# seq_s-h_1-13-21-fix.net
KiCad netlist of a schematic drawn in EAGLE
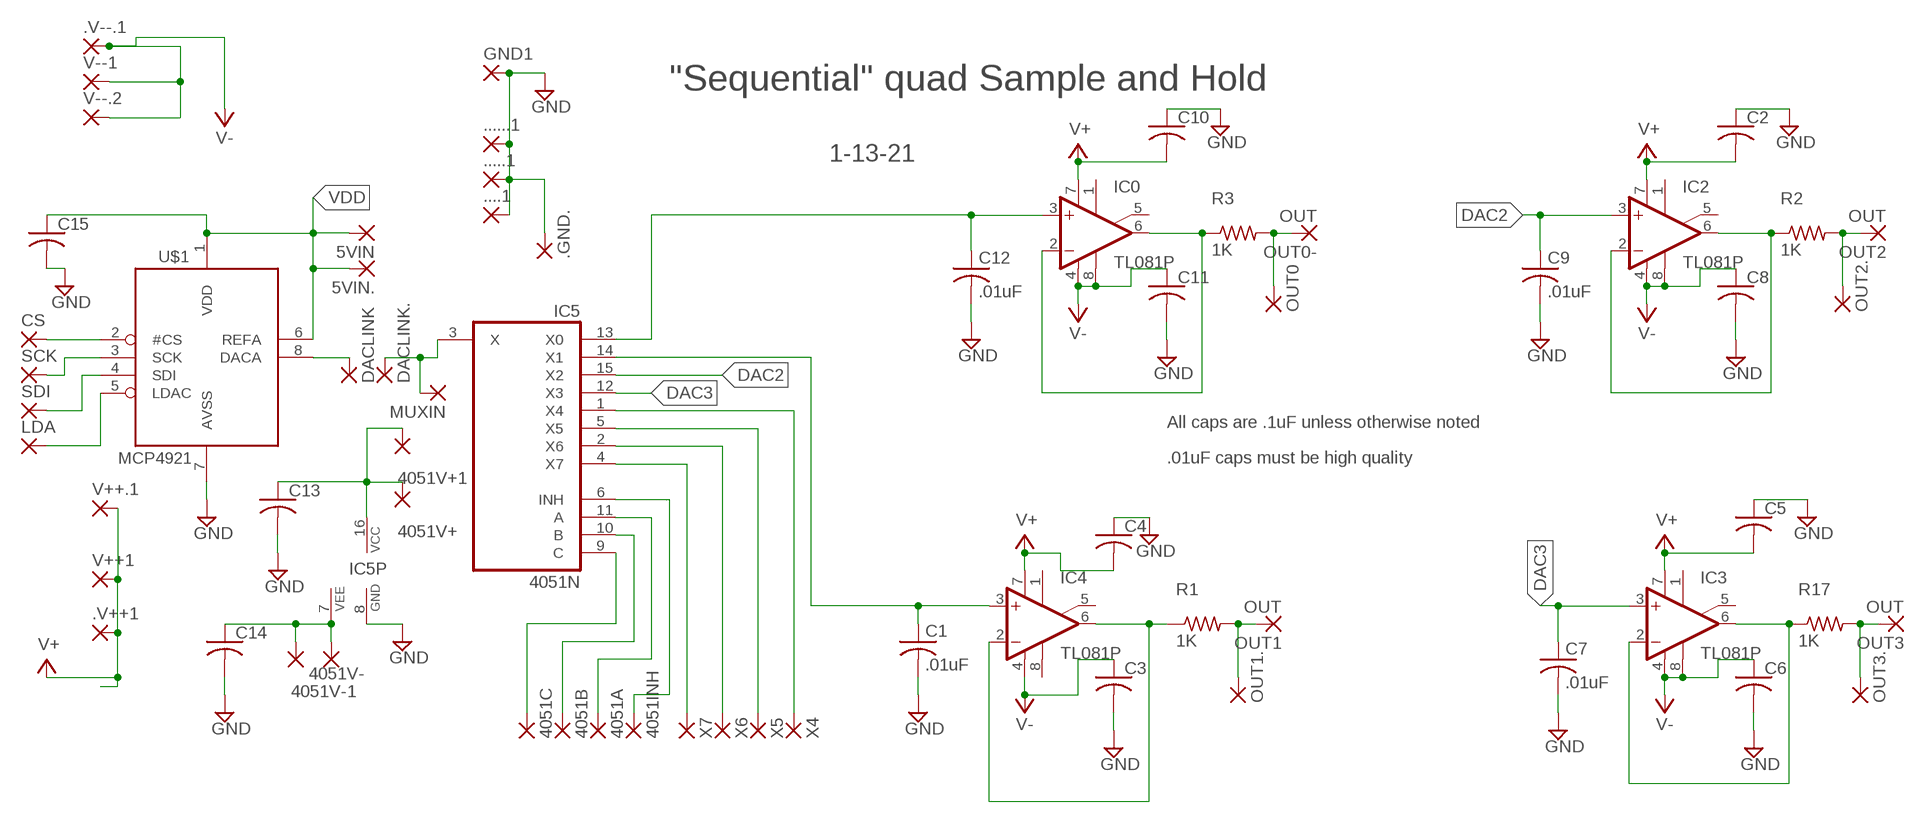
[diagram p0: schematic, sheet 1]

(export (version "E")
  (design (tool "Eeschema 10.0.6"))
  (components
    (comp (ref "......1")
      (value "3,17/1,3")
      (footprint "eagle-import:3,17_1,3")
      (libsource (lib "eagle-import") (part "wirepad_412_3,17/1,3"))
    )
    (comp (ref ".....1")
      (value "3,17/1,3")
      (footprint "eagle-import:3,17_1,3")
      (libsource (lib "eagle-import") (part "wirepad_412_3,17/1,3"))
    )
    (comp (ref "....1")
      (value "3,17/1,3")
      (footprint "eagle-import:3,17_1,3")
      (libsource (lib "eagle-import") (part "wirepad_412_3,17/1,3"))
    )
    (comp (ref ".GND.")
      (value "WIREPAD1,6/0,9")
      (footprint "eagle-import:1,6_0,9")
      (libsource (lib "eagle-import") (part "WIREPAD1,6/0,9"))
    )
    (comp (ref ".V++1")
      (value "2,54/1,0")
      (footprint "eagle-import:2,54_1,0")
      (libsource (lib "eagle-import") (part "2,54/1,0"))
    )
    (comp (ref ".V--.1")
      (value "3,17/1,3")
      (footprint "eagle-import:3,17_1,3")
      (libsource (lib "eagle-import") (part "3,17/1,3"))
    )
    (comp (ref "5VIN")
      (value "WIREPAD3,17/1,3")
      (footprint "eagle-import:3,17_1,3@1")
      (libsource (lib "eagle-import") (part "WIREPAD3,17/1,3"))
    )
    (comp (ref "5VIN.")
      (value "WIREPAD1,6/0,9")
      (footprint "eagle-import:1,6_0,9")
      (libsource (lib "eagle-import") (part "WIREPAD1,6/0,9"))
    )
    (comp (ref "4051A")
      (value "WIREPAD1,6/0,9")
      (footprint "eagle-import:1,6_0,9")
      (libsource (lib "eagle-import") (part "WIREPAD1,6/0,9"))
    )
    (comp (ref "4051B")
      (value "WIREPAD1,6/0,9")
      (footprint "eagle-import:1,6_0,9")
      (libsource (lib "eagle-import") (part "WIREPAD1,6/0,9"))
    )
    (comp (ref "4051C")
      (value "WIREPAD1,6/0,9")
      (footprint "eagle-import:1,6_0,9")
      (libsource (lib "eagle-import") (part "WIREPAD1,6/0,9"))
    )
    (comp (ref "4051INH")
      (value "WIREPAD1,6/0,9")
      (footprint "eagle-import:1,6_0,9")
      (libsource (lib "eagle-import") (part "WIREPAD1,6/0,9"))
    )
    (comp (ref "4051V+")
      (value "3,17/1,3")
      (footprint "eagle-import:3,17_1,3")
      (libsource (lib "eagle-import") (part "wirepad_412_3,17/1,3"))
    )
    (comp (ref "4051V+1")
      (value "WIREPAD1,6/0,9")
      (footprint "eagle-import:1,6_0,9")
      (libsource (lib "eagle-import") (part "WIREPAD1,6/0,9"))
    )
    (comp (ref "4051V-")
      (value "3,17/1,3")
      (footprint "eagle-import:3,17_1,3")
      (libsource (lib "eagle-import") (part "wirepad_412_3,17/1,3"))
    )
    (comp (ref "4051V-1")
      (value "WIREPAD1,6/0,9")
      (footprint "eagle-import:1,6_0,9")
      (libsource (lib "eagle-import") (part "WIREPAD1,6/0,9"))
    )
    (comp (ref "C1")
      (value ".01uF")
      (footprint "eagle-import:C050-025X075")
      (libsource (lib "eagle-import") (part "C-US050-025X075"))
    )
    (comp (ref "C2")
      (value "C-US025-024X044")
      (footprint "eagle-import:C025-024X044")
      (libsource (lib "eagle-import") (part "C-US025-024X044"))
    )
    (comp (ref "C3")
      (value "C-US025-024X044")
      (footprint "eagle-import:C025-024X044")
      (libsource (lib "eagle-import") (part "C-US025-024X044"))
    )
    (comp (ref "C4")
      (value "C-US025-024X044")
      (footprint "eagle-import:C025-024X044")
      (libsource (lib "eagle-import") (part "C-US025-024X044"))
    )
    (comp (ref "C5")
      (value "C-US025-024X044")
      (footprint "eagle-import:C025-024X044")
      (libsource (lib "eagle-import") (part "C-US025-024X044"))
    )
    (comp (ref "C6")
      (value "C-US025-024X044")
      (footprint "eagle-import:C025-024X044")
      (libsource (lib "eagle-import") (part "C-US025-024X044"))
    )
    (comp (ref "C7")
      (value ".01uF")
      (footprint "eagle-import:C050-025X075")
      (libsource (lib "eagle-import") (part "C-US050-025X075"))
    )
    (comp (ref "C8")
      (value "C-US025-024X044")
      (footprint "eagle-import:C025-024X044")
      (libsource (lib "eagle-import") (part "C-US025-024X044"))
    )
    (comp (ref "C9")
      (value ".01uF")
      (footprint "eagle-import:C050-025X075")
      (libsource (lib "eagle-import") (part "C-US050-025X075"))
    )
    (comp (ref "C10")
      (value "C-US025-024X044")
      (footprint "eagle-import:C025-024X044")
      (libsource (lib "eagle-import") (part "C-US025-024X044"))
    )
    (comp (ref "C11")
      (value "C-US025-024X044")
      (footprint "eagle-import:C025-024X044")
      (libsource (lib "eagle-import") (part "C-US025-024X044"))
    )
    (comp (ref "C12")
      (value ".01uF")
      (footprint "eagle-import:C050-025X075")
      (libsource (lib "eagle-import") (part "C-US050-025X075"))
    )
    (comp (ref "C13")
      (value "C-US025-024X044")
      (footprint "eagle-import:C025-024X044")
      (libsource (lib "eagle-import") (part "C-US025-024X044"))
    )
    (comp (ref "C14")
      (value "C-US025-024X044")
      (footprint "eagle-import:C025-024X044")
      (libsource (lib "eagle-import") (part "C-US025-024X044"))
    )
    (comp (ref "C15")
      (value "C-US025-024X044")
      (footprint "eagle-import:C025-024X044")
      (libsource (lib "eagle-import") (part "C-US025-024X044"))
    )
    (comp (ref "CS")
      (value "WIREPAD1,6/0,9")
      (footprint "eagle-import:1,6_0,9")
      (libsource (lib "eagle-import") (part "WIREPAD1,6/0,9"))
    )
    (comp (ref "DACLINK")
      (value "WIREPAD1,6/0,9")
      (footprint "eagle-import:1,6_0,9")
      (libsource (lib "eagle-import") (part "WIREPAD1,6/0,9"))
    )
    (comp (ref "DACLINK.")
      (value "WIREPAD1,6/0,9")
      (footprint "eagle-import:1,6_0,9")
      (libsource (lib "eagle-import") (part "WIREPAD1,6/0,9"))
    )
    (comp (ref "GND1")
      (value "3,17/1,3")
      (footprint "eagle-import:3,17_1,3")
      (libsource (lib "eagle-import") (part "wirepad_412_3,17/1,3"))
    )
    (comp (ref "IC0")
      (value "TL081P")
      (footprint "eagle-import:DIL08")
      (libsource (lib "eagle-import") (part "TL081P"))
    )
    (comp (ref "IC2")
      (value "TL081P")
      (footprint "eagle-import:DIL08")
      (libsource (lib "eagle-import") (part "TL081P"))
    )
    (comp (ref "IC3")
      (value "TL081P")
      (footprint "eagle-import:DIL08")
      (libsource (lib "eagle-import") (part "TL081P"))
    )
    (comp (ref "IC4")
      (value "TL081P")
      (footprint "eagle-import:DIL08")
      (libsource (lib "eagle-import") (part "TL081P"))
    )
    (comp (ref "IC5")
      (value "4051N")
      (footprint "eagle-import:DIL16")
      (libsource (lib "eagle-import") (part "4051N"))
    )
    (comp (ref "LDA")
      (value "WIREPAD1,6/0,9")
      (footprint "eagle-import:1,6_0,9")
      (libsource (lib "eagle-import") (part "WIREPAD1,6/0,9"))
    )
    (comp (ref "MUXIN")
      (value "3,17/1,3")
      (footprint "eagle-import:3,17_1,3")
      (libsource (lib "eagle-import") (part "wirepad_412_3,17/1,3"))
    )
    (comp (ref "OUT0")
      (value "WIREPAD1,6/0,9")
      (footprint "eagle-import:1,6_0,9")
      (libsource (lib "eagle-import") (part "WIREPAD1,6/0,9"))
    )
    (comp (ref "OUT0-")
      (value "OUT")
      (footprint "eagle-import:3,17_1,3")
      (libsource (lib "eagle-import") (part "wirepad_412_3,17/1,3"))
    )
    (comp (ref "OUT1")
      (value "OUT")
      (footprint "eagle-import:3,17_1,3")
      (libsource (lib "eagle-import") (part "wirepad_412_3,17/1,3"))
    )
    (comp (ref "OUT1.")
      (value "WIREPAD1,6/0,9")
      (footprint "eagle-import:1,6_0,9")
      (libsource (lib "eagle-import") (part "WIREPAD1,6/0,9"))
    )
    (comp (ref "OUT2")
      (value "OUT")
      (footprint "eagle-import:3,17_1,3")
      (libsource (lib "eagle-import") (part "wirepad_412_3,17/1,3"))
    )
    (comp (ref "OUT2.")
      (value "WIREPAD1,6/0,9")
      (footprint "eagle-import:1,6_0,9")
      (libsource (lib "eagle-import") (part "WIREPAD1,6/0,9"))
    )
    (comp (ref "OUT3")
      (value "OUT")
      (footprint "eagle-import:3,17_1,3")
      (libsource (lib "eagle-import") (part "wirepad_412_3,17/1,3"))
    )
    (comp (ref "OUT3.")
      (value "WIREPAD1,6/0,9")
      (footprint "eagle-import:1,6_0,9")
      (libsource (lib "eagle-import") (part "WIREPAD1,6/0,9"))
    )
    (comp (ref "R1")
      (value "1K")
      (footprint "eagle-import:0204_7")
      (libsource (lib "eagle-import") (part "R-US_0204/7"))
    )
    (comp (ref "R2")
      (value "1K")
      (footprint "eagle-import:0204_7")
      (libsource (lib "eagle-import") (part "R-US_0204/7"))
    )
    (comp (ref "R3")
      (value "1K")
      (footprint "eagle-import:0204_7")
      (libsource (lib "eagle-import") (part "R-US_0204/7"))
    )
    (comp (ref "R17")
      (value "1K")
      (footprint "eagle-import:0204_7")
      (libsource (lib "eagle-import") (part "R-US_0204/7"))
    )
    (comp (ref "SCK")
      (value "WIREPAD1,6/0,9")
      (footprint "eagle-import:1,6_0,9")
      (libsource (lib "eagle-import") (part "WIREPAD1,6/0,9"))
    )
    (comp (ref "SDI")
      (value "WIREPAD1,6/0,9")
      (footprint "eagle-import:1,6_0,9")
      (libsource (lib "eagle-import") (part "WIREPAD1,6/0,9"))
    )
    (comp (ref "U$1")
      (value "MCP4921")
      (footprint "eagle-import:DIL08")
      (libsource (lib "eagle-import") (part "MCP4921"))
    )
    (comp (ref "V++.1")
      (value "2,54/1,0")
      (footprint "eagle-import:2,54_1,0")
      (libsource (lib "eagle-import") (part "2,54/1,0"))
    )
    (comp (ref "V++1")
      (value "2,54/1,0")
      (footprint "eagle-import:2,54_1,0")
      (libsource (lib "eagle-import") (part "2,54/1,0"))
    )
    (comp (ref "V--.2")
      (value "3,17/1,3")
      (footprint "eagle-import:3,17_1,3")
      (libsource (lib "eagle-import") (part "3,17/1,3"))
    )
    (comp (ref "V--1")
      (value "3,17/1,3")
      (footprint "eagle-import:3,17_1,3")
      (libsource (lib "eagle-import") (part "3,17/1,3"))
    )
    (comp (ref "X4")
      (value "WIREPAD1,6/0,9")
      (footprint "eagle-import:1,6_0,9")
      (libsource (lib "eagle-import") (part "WIREPAD1,6/0,9"))
    )
    (comp (ref "X5")
      (value "WIREPAD1,6/0,9")
      (footprint "eagle-import:1,6_0,9")
      (libsource (lib "eagle-import") (part "WIREPAD1,6/0,9"))
    )
    (comp (ref "X6")
      (value "WIREPAD1,6/0,9")
      (footprint "eagle-import:1,6_0,9")
      (libsource (lib "eagle-import") (part "WIREPAD1,6/0,9"))
    )
    (comp (ref "X7")
      (value "WIREPAD1,6/0,9")
      (footprint "eagle-import:1,6_0,9")
      (libsource (lib "eagle-import") (part "WIREPAD1,6/0,9"))
    )
  )
  (nets
    (net (code "1") (name "DAC2") (class "Default")
      (node (ref "C9") (pin "1") (pinfunction "1_1") (pintype "passive"))
      (node (ref "IC2") (pin "3") (pinfunction "+IN_3") (pintype "input"))
      (node (ref "IC5") (pin "15") (pinfunction "X2_15") (pintype "bidirectional"))
    )
    (net (code "2") (name "DAC3") (class "Default")
      (node (ref "C7") (pin "1") (pinfunction "1_1") (pintype "passive"))
      (node (ref "IC3") (pin "3") (pinfunction "+IN_3") (pintype "input"))
      (node (ref "IC5") (pin "12") (pinfunction "X3_12") (pintype "bidirectional"))
    )
    (net (code "3") (name "GND") (class "Default")
      (node (ref "......1") (pin "1") (pinfunction "P_1") (pintype "passive"))
      (node (ref ".....1") (pin "1") (pinfunction "P_1") (pintype "passive"))
      (node (ref "....1") (pin "1") (pinfunction "P_1") (pintype "passive"))
      (node (ref ".GND.") (pin "1") (pinfunction "P_1") (pintype "passive"))
      (node (ref "C1") (pin "2") (pinfunction "2_2") (pintype "passive"))
      (node (ref "C10") (pin "1") (pinfunction "1_1") (pintype "passive"))
      (node (ref "C11") (pin "2") (pinfunction "2_2") (pintype "passive"))
      (node (ref "C12") (pin "2") (pinfunction "2_2") (pintype "passive"))
      (node (ref "C13") (pin "2") (pinfunction "2_2") (pintype "passive"))
      (node (ref "C14") (pin "2") (pinfunction "2_2") (pintype "passive"))
      (node (ref "C15") (pin "2") (pinfunction "2_2") (pintype "passive"))
      (node (ref "C2") (pin "1") (pinfunction "1_1") (pintype "passive"))
      (node (ref "C3") (pin "2") (pinfunction "2_2") (pintype "passive"))
      (node (ref "C4") (pin "1") (pinfunction "1_1") (pintype "passive"))
      (node (ref "C5") (pin "1") (pinfunction "1_1") (pintype "passive"))
      (node (ref "C6") (pin "2") (pinfunction "2_2") (pintype "passive"))
      (node (ref "C7") (pin "2") (pinfunction "2_2") (pintype "passive"))
      (node (ref "C8") (pin "2") (pinfunction "2_2") (pintype "passive"))
      (node (ref "C9") (pin "2") (pinfunction "2_2") (pintype "passive"))
      (node (ref "GND1") (pin "1") (pinfunction "P_1") (pintype "passive"))
      (node (ref "IC5") (pin "8") (pinfunction "GND_8") (pintype "power_in"))
      (node (ref "U$1") (pin "7") (pinfunction "AVSS_7") (pintype "power_in"))
    )
    (net (code "4") (name "Net-(4051A-P)") (class "Default")
      (node (ref "4051A") (pin "1") (pinfunction "P_1") (pintype "passive"))
      (node (ref "IC5") (pin "11") (pinfunction "A_11") (pintype "input"))
    )
    (net (code "5") (name "Net-(4051B-P)") (class "Default")
      (node (ref "4051B") (pin "1") (pinfunction "P_1") (pintype "passive"))
      (node (ref "IC5") (pin "10") (pinfunction "B_10") (pintype "input"))
    )
    (net (code "6") (name "Net-(4051C-P)") (class "Default")
      (node (ref "4051C") (pin "1") (pinfunction "P_1") (pintype "passive"))
      (node (ref "IC5") (pin "9") (pinfunction "C_9") (pintype "input"))
    )
    (net (code "7") (name "Net-(4051INH-P)") (class "Default")
      (node (ref "4051INH") (pin "1") (pinfunction "P_1") (pintype "passive"))
      (node (ref "IC5") (pin "6") (pinfunction "INH_6") (pintype "input"))
    )
    (net (code "8") (name "Net-(4051V+-P)") (class "Default")
      (node (ref "4051V+") (pin "1") (pinfunction "P_1") (pintype "passive"))
      (node (ref "4051V+1") (pin "1") (pinfunction "P_1") (pintype "passive"))
      (node (ref "C13") (pin "1") (pinfunction "1_1") (pintype "passive"))
      (node (ref "IC5") (pin "16") (pinfunction "VCC_16") (pintype "power_in"))
    )
    (net (code "9") (name "Net-(4051V--P)") (class "Default")
      (node (ref "4051V-") (pin "1") (pinfunction "P_1") (pintype "passive"))
      (node (ref "4051V-1") (pin "1") (pinfunction "P_1") (pintype "passive"))
      (node (ref "C14") (pin "1") (pinfunction "1_1") (pintype "passive"))
      (node (ref "IC5") (pin "7") (pinfunction "VEE_7") (pintype "power_in"))
    )
    (net (code "10") (name "Net-(CS-P)") (class "Default")
      (node (ref "CS") (pin "1") (pinfunction "P_1") (pintype "passive"))
      (node (ref "U$1") (pin "2") (pinfunction "#CS_2") (pintype "input"))
    )
    (net (code "11") (name "Net-(DACLINK-P)") (class "Default")
      (node (ref "DACLINK") (pin "1") (pinfunction "P_1") (pintype "passive"))
      (node (ref "U$1") (pin "8") (pinfunction "DACA_8") (pintype "output"))
    )
    (net (code "12") (name "Net-(DACLINK.-P)") (class "Default")
      (node (ref "DACLINK.") (pin "1") (pinfunction "P_1") (pintype "passive"))
      (node (ref "IC5") (pin "3") (pinfunction "X_3") (pintype "bidirectional"))
      (node (ref "MUXIN") (pin "1") (pinfunction "P_1") (pintype "passive"))
    )
    (net (code "13") (name "Net-(IC0-+IN)") (class "Default")
      (node (ref "C12") (pin "1") (pinfunction "1_1") (pintype "passive"))
      (node (ref "IC0") (pin "3") (pinfunction "+IN_3") (pintype "input"))
      (node (ref "IC5") (pin "13") (pinfunction "X0_13") (pintype "bidirectional"))
    )
    (net (code "14") (name "Net-(IC0--IN)") (class "Default")
      (node (ref "IC0") (pin "2") (pinfunction "-IN_2") (pintype "input"))
      (node (ref "IC0") (pin "6") (pinfunction "OUT_6") (pintype "output"))
      (node (ref "R3") (pin "1") (pinfunction "1_1") (pintype "passive"))
    )
    (net (code "15") (name "Net-(IC2--IN)") (class "Default")
      (node (ref "IC2") (pin "2") (pinfunction "-IN_2") (pintype "input"))
      (node (ref "IC2") (pin "6") (pinfunction "OUT_6") (pintype "output"))
      (node (ref "R2") (pin "1") (pinfunction "1_1") (pintype "passive"))
    )
    (net (code "16") (name "Net-(IC3--IN)") (class "Default")
      (node (ref "IC3") (pin "2") (pinfunction "-IN_2") (pintype "input"))
      (node (ref "IC3") (pin "6") (pinfunction "OUT_6") (pintype "output"))
      (node (ref "R17") (pin "1") (pinfunction "1_1") (pintype "passive"))
    )
    (net (code "17") (name "Net-(IC4-+IN)") (class "Default")
      (node (ref "C1") (pin "1") (pinfunction "1_1") (pintype "passive"))
      (node (ref "IC4") (pin "3") (pinfunction "+IN_3") (pintype "input"))
      (node (ref "IC5") (pin "14") (pinfunction "X1_14") (pintype "bidirectional"))
    )
    (net (code "18") (name "Net-(IC4--IN)") (class "Default")
      (node (ref "IC4") (pin "2") (pinfunction "-IN_2") (pintype "input"))
      (node (ref "IC4") (pin "6") (pinfunction "OUT_6") (pintype "output"))
      (node (ref "R1") (pin "1") (pinfunction "1_1") (pintype "passive"))
    )
    (net (code "19") (name "Net-(IC5A-X4)") (class "Default")
      (node (ref "IC5") (pin "1") (pinfunction "X4_1") (pintype "bidirectional"))
      (node (ref "X4") (pin "1") (pinfunction "P_1") (pintype "passive"))
    )
    (net (code "20") (name "Net-(IC5A-X5)") (class "Default")
      (node (ref "IC5") (pin "5") (pinfunction "X5_5") (pintype "bidirectional"))
      (node (ref "X5") (pin "1") (pinfunction "P_1") (pintype "passive"))
    )
    (net (code "21") (name "Net-(IC5A-X6)") (class "Default")
      (node (ref "IC5") (pin "2") (pinfunction "X6_2") (pintype "bidirectional"))
      (node (ref "X6") (pin "1") (pinfunction "P_1") (pintype "passive"))
    )
    (net (code "22") (name "Net-(IC5A-X7)") (class "Default")
      (node (ref "IC5") (pin "4") (pinfunction "X7_4") (pintype "bidirectional"))
      (node (ref "X7") (pin "1") (pinfunction "P_1") (pintype "passive"))
    )
    (net (code "23") (name "Net-(LDA-P)") (class "Default")
      (node (ref "LDA") (pin "1") (pinfunction "P_1") (pintype "passive"))
      (node (ref "U$1") (pin "5") (pinfunction "LDAC_5") (pintype "input"))
    )
    (net (code "24") (name "Net-(OUT0--P)") (class "Default")
      (node (ref "OUT0") (pin "1") (pinfunction "P_1") (pintype "passive"))
      (node (ref "OUT0-") (pin "1") (pinfunction "P_1") (pintype "passive"))
      (node (ref "R3") (pin "2") (pinfunction "2_2") (pintype "passive"))
    )
    (net (code "25") (name "Net-(OUT1-P)") (class "Default")
      (node (ref "OUT1") (pin "1") (pinfunction "P_1") (pintype "passive"))
      (node (ref "OUT1.") (pin "1") (pinfunction "P_1") (pintype "passive"))
      (node (ref "R1") (pin "2") (pinfunction "2_2") (pintype "passive"))
    )
    (net (code "26") (name "Net-(OUT2-P)") (class "Default")
      (node (ref "OUT2") (pin "1") (pinfunction "P_1") (pintype "passive"))
      (node (ref "OUT2.") (pin "1") (pinfunction "P_1") (pintype "passive"))
      (node (ref "R2") (pin "2") (pinfunction "2_2") (pintype "passive"))
    )
    (net (code "27") (name "Net-(OUT3-P)") (class "Default")
      (node (ref "OUT3") (pin "1") (pinfunction "P_1") (pintype "passive"))
      (node (ref "OUT3.") (pin "1") (pinfunction "P_1") (pintype "passive"))
      (node (ref "R17") (pin "2") (pinfunction "2_2") (pintype "passive"))
    )
    (net (code "28") (name "Net-(SCK-P)") (class "Default")
      (node (ref "SCK") (pin "1") (pinfunction "P_1") (pintype "passive"))
      (node (ref "U$1") (pin "3") (pinfunction "SCK_3") (pintype "input"))
    )
    (net (code "29") (name "Net-(SDI-P)") (class "Default")
      (node (ref "SDI") (pin "1") (pinfunction "P_1") (pintype "passive"))
      (node (ref "U$1") (pin "4") (pinfunction "SDI_4") (pintype "input"))
    )
    (net (code "30") (name "V+") (class "Default")
      (node (ref ".V++1") (pin "1") (pinfunction "P_1") (pintype "passive"))
      (node (ref "C10") (pin "2") (pinfunction "2_2") (pintype "passive"))
      (node (ref "C2") (pin "2") (pinfunction "2_2") (pintype "passive"))
      (node (ref "C4") (pin "2") (pinfunction "2_2") (pintype "passive"))
      (node (ref "C5") (pin "2") (pinfunction "2_2") (pintype "passive"))
      (node (ref "IC0") (pin "7") (pinfunction "V+_7") (pintype "power_in"))
      (node (ref "IC2") (pin "7") (pinfunction "V+_7") (pintype "power_in"))
      (node (ref "IC3") (pin "7") (pinfunction "V+_7") (pintype "power_in"))
      (node (ref "IC4") (pin "7") (pinfunction "V+_7") (pintype "power_in"))
      (node (ref "V++.1") (pin "1") (pinfunction "P_1") (pintype "passive"))
      (node (ref "V++1") (pin "1") (pinfunction "P_1") (pintype "passive"))
    )
    (net (code "31") (name "V-") (class "Default")
      (node (ref ".V--.1") (pin "1") (pinfunction "P_1") (pintype "passive"))
      (node (ref "C11") (pin "1") (pinfunction "1_1") (pintype "passive"))
      (node (ref "C3") (pin "1") (pinfunction "1_1") (pintype "passive"))
      (node (ref "C6") (pin "1") (pinfunction "1_1") (pintype "passive"))
      (node (ref "C8") (pin "1") (pinfunction "1_1") (pintype "passive"))
      (node (ref "IC0") (pin "4") (pinfunction "V-_4") (pintype "power_in"))
      (node (ref "IC0") (pin "8") (pinfunction "OPT_8") (pintype "passive"))
      (node (ref "IC2") (pin "4") (pinfunction "V-_4") (pintype "power_in"))
      (node (ref "IC2") (pin "8") (pinfunction "OPT_8") (pintype "passive"))
      (node (ref "IC3") (pin "4") (pinfunction "V-_4") (pintype "power_in"))
      (node (ref "IC3") (pin "8") (pinfunction "OPT_8") (pintype "passive"))
      (node (ref "IC4") (pin "4") (pinfunction "V-_4") (pintype "power_in"))
      (node (ref "V--.2") (pin "1") (pinfunction "P_1") (pintype "passive"))
      (node (ref "V--1") (pin "1") (pinfunction "P_1") (pintype "passive"))
    )
    (net (code "32") (name "VDD") (class "Default")
      (node (ref "5VIN") (pin "1") (pinfunction "P_1") (pintype "passive"))
      (node (ref "5VIN.") (pin "1") (pinfunction "P_1") (pintype "passive"))
      (node (ref "C15") (pin "1") (pinfunction "1_1") (pintype "passive"))
      (node (ref "U$1") (pin "1") (pinfunction "VDD_1") (pintype "power_in"))
      (node (ref "U$1") (pin "6") (pinfunction "REFA_6") (pintype "input"))
    )
    (net (code "33") (name "unconnected-(IC0-ON1-Pad1)") (class "Default")
      (node (ref "IC0") (pin "1") (pinfunction "ON1_1") (pintype "passive"))
    )
    (net (code "34") (name "unconnected-(IC0-ON2-Pad5)") (class "Default")
      (node (ref "IC0") (pin "5") (pinfunction "ON2_5") (pintype "passive"))
    )
    (net (code "35") (name "unconnected-(IC2-ON1-Pad1)") (class "Default")
      (node (ref "IC2") (pin "1") (pinfunction "ON1_1") (pintype "passive"))
    )
    (net (code "36") (name "unconnected-(IC2-ON2-Pad5)") (class "Default")
      (node (ref "IC2") (pin "5") (pinfunction "ON2_5") (pintype "passive"))
    )
    (net (code "37") (name "unconnected-(IC3-ON1-Pad1)") (class "Default")
      (node (ref "IC3") (pin "1") (pinfunction "ON1_1") (pintype "passive"))
    )
    (net (code "38") (name "unconnected-(IC3-ON2-Pad5)") (class "Default")
      (node (ref "IC3") (pin "5") (pinfunction "ON2_5") (pintype "passive"))
    )
    (net (code "39") (name "unconnected-(IC4-ON1-Pad1)") (class "Default")
      (node (ref "IC4") (pin "1") (pinfunction "ON1_1") (pintype "passive"))
    )
    (net (code "40") (name "unconnected-(IC4-ON2-Pad5)") (class "Default")
      (node (ref "IC4") (pin "5") (pinfunction "ON2_5") (pintype "passive"))
    )
    (net (code "41") (name "unconnected-(IC4-OPT-Pad8)") (class "Default")
      (node (ref "IC4") (pin "8") (pinfunction "OPT_8") (pintype "passive"))
    )
  )
)
